# Crystal_Driver.net
KiCad netlist of a schematic drawn in EAGLE
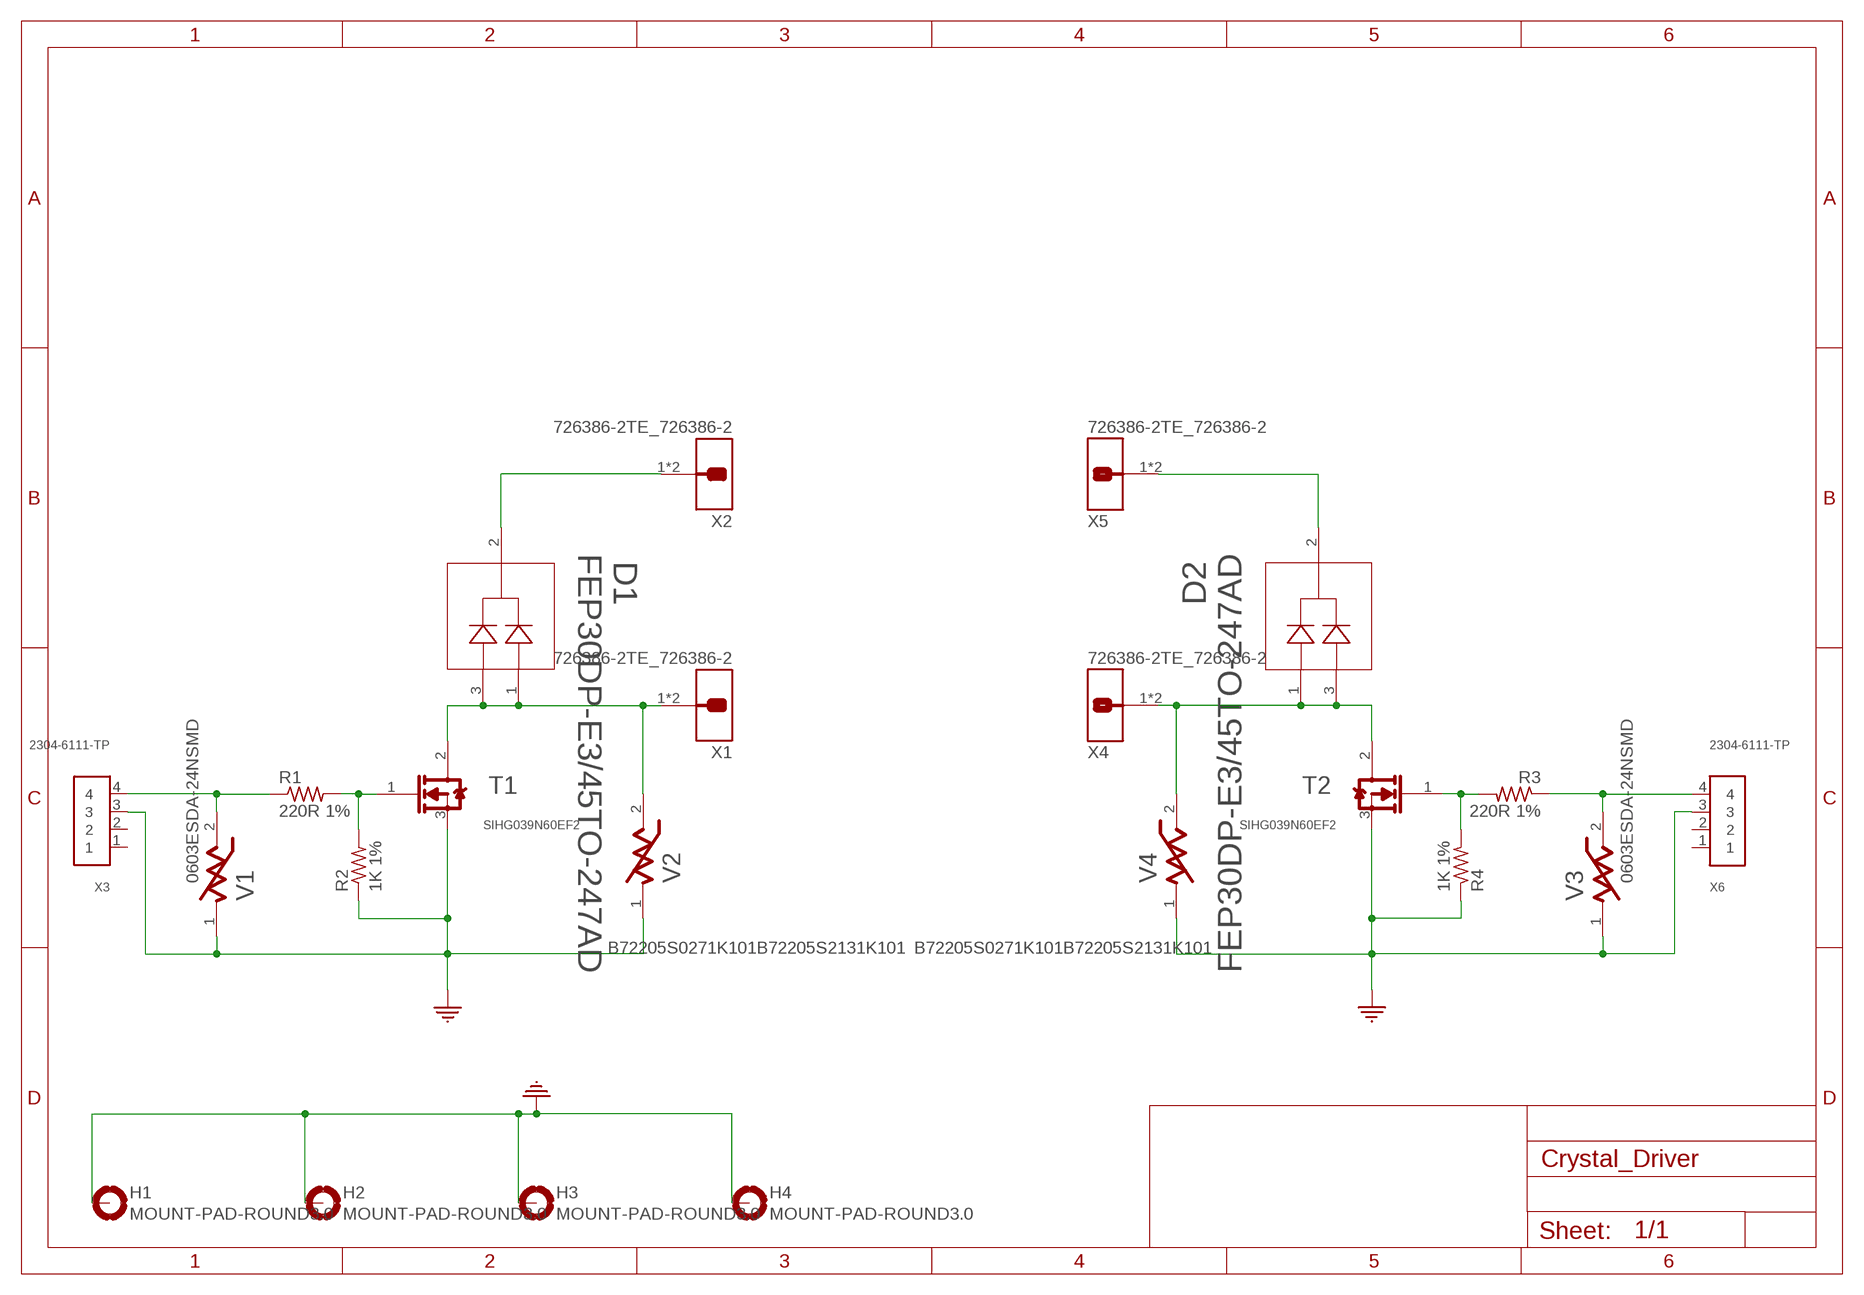
[diagram p0: schematic, sheet 1]

(export (version "E")
  (design (tool "Eeschema 10.0.6"))
  (components
    (comp (ref "D1")
      (value "FEP30DP-E3/45TO-247AD")
      (footprint "eagle-import:TO-247AD")
      (libsource (lib "eagle-import") (part "FEP30DP-E3/45TO-247AD"))
    )
    (comp (ref "D2")
      (value "FEP30DP-E3/45TO-247AD")
      (footprint "eagle-import:TO-247AD")
      (libsource (lib "eagle-import") (part "FEP30DP-E3/45TO-247AD"))
    )
    (comp (ref "H1")
      (value "MOUNT-PAD-ROUND3.0")
      (footprint "eagle-import:3,0-PAD")
      (libsource (lib "eagle-import") (part "MOUNT-PAD-ROUND3.0"))
    )
    (comp (ref "H2")
      (value "MOUNT-PAD-ROUND3.0")
      (footprint "eagle-import:3,0-PAD")
      (libsource (lib "eagle-import") (part "MOUNT-PAD-ROUND3.0"))
    )
    (comp (ref "H3")
      (value "MOUNT-PAD-ROUND3.0")
      (footprint "eagle-import:3,0-PAD")
      (libsource (lib "eagle-import") (part "MOUNT-PAD-ROUND3.0"))
    )
    (comp (ref "H4")
      (value "MOUNT-PAD-ROUND3.0")
      (footprint "eagle-import:3,0-PAD")
      (libsource (lib "eagle-import") (part "MOUNT-PAD-ROUND3.0"))
    )
    (comp (ref "R1")
      (value "220R 1%")
      (footprint "eagle-import:EIA1206")
      (libsource (lib "eagle-import") (part "R_1206EIA1206"))
    )
    (comp (ref "R2")
      (value "1K 1%")
      (footprint "eagle-import:EIA0603")
      (libsource (lib "eagle-import") (part "R_0603"))
    )
    (comp (ref "R3")
      (value "220R 1%")
      (footprint "eagle-import:EIA1206")
      (libsource (lib "eagle-import") (part "R_1206EIA1206"))
    )
    (comp (ref "R4")
      (value "1K 1%")
      (footprint "eagle-import:EIA0603")
      (libsource (lib "eagle-import") (part "R_0603"))
    )
    (comp (ref "T1")
      (value "SIHG039N60EF2")
      (footprint "eagle-import:TO-247AC")
      (libsource (lib "eagle-import") (part "SIHG039N60EF2"))
    )
    (comp (ref "T2")
      (value "SIHG039N60EF2")
      (footprint "eagle-import:TO-247AC")
      (libsource (lib "eagle-import") (part "SIHG039N60EF2"))
    )
    (comp (ref "V1")
      (value "0603ESDA-24NSMD")
      (footprint "eagle-import:EIA0603")
      (fields (field (name "MFR") "Bourns"))
      (libsource (lib "eagle-import") (part "0603ESDA-24NSMD"))
    )
    (comp (ref "V2")
      (value "B72205S0271K101B72205S2131K101")
      (footprint "eagle-import:EPCOS_B72205S0271K101_0")
      (fields (field (name "MFR") "EPCOS"))
      (libsource (lib "eagle-import") (part "B72205S0271K101B72205S2131K101"))
    )
    (comp (ref "V3")
      (value "0603ESDA-24NSMD")
      (footprint "eagle-import:EIA0603")
      (fields (field (name "MFR") "Bourns"))
      (libsource (lib "eagle-import") (part "0603ESDA-24NSMD"))
    )
    (comp (ref "V4")
      (value "B72205S0271K101B72205S2131K101")
      (footprint "eagle-import:EPCOS_B72205S0271K101_0")
      (fields (field (name "MFR") "EPCOS"))
      (libsource (lib "eagle-import") (part "B72205S0271K101B72205S2131K101"))
    )
    (comp (ref "X1")
      (value "726386-2TE_726386-2")
      (footprint "eagle-import:TE_726386-2")
      (fields
        (field (name "DIGIKEY_PART_NUMBER") "A114371-ND")
        (field (name "MF") "TE")
        (field (name "MOUSER_PART_NUMBER") "571-726386-2")
      )
      (libsource (lib "eagle-import") (part "726386-2TE_726386-2"))
    )
    (comp (ref "X2")
      (value "726386-2TE_726386-2")
      (footprint "eagle-import:TE_726386-2")
      (fields
        (field (name "DIGIKEY_PART_NUMBER") "A114371-ND")
        (field (name "MF") "TE")
        (field (name "MOUSER_PART_NUMBER") "571-726386-2")
      )
      (libsource (lib "eagle-import") (part "726386-2TE_726386-2"))
    )
    (comp (ref "X3")
      (value "2304-6111-TP")
      (footprint "eagle-import:X04_100MIL")
      (fields (field (name "MFR") "3M"))
      (libsource (lib "eagle-import") (part "2304-6111-TP"))
    )
    (comp (ref "X4")
      (value "726386-2TE_726386-2")
      (footprint "eagle-import:TE_726386-2")
      (fields
        (field (name "DIGIKEY_PART_NUMBER") "A114371-ND")
        (field (name "MF") "TE")
        (field (name "MOUSER_PART_NUMBER") "571-726386-2")
      )
      (libsource (lib "eagle-import") (part "726386-2TE_726386-2"))
    )
    (comp (ref "X5")
      (value "726386-2TE_726386-2")
      (footprint "eagle-import:TE_726386-2")
      (fields
        (field (name "DIGIKEY_PART_NUMBER") "A114371-ND")
        (field (name "MF") "TE")
        (field (name "MOUSER_PART_NUMBER") "571-726386-2")
      )
      (libsource (lib "eagle-import") (part "726386-2TE_726386-2"))
    )
    (comp (ref "X6")
      (value "2304-6111-TP")
      (footprint "eagle-import:X04_100MIL")
      (fields (field (name "MFR") "3M"))
      (libsource (lib "eagle-import") (part "2304-6111-TP"))
    )
  )
  (nets
    (net (code "1") (name "GND") (class "Default")
      (node (ref "H1") (pin "B3,0") (pinfunction "MOUNT_B3,0") (pintype "passive"))
      (node (ref "H2") (pin "B3,0") (pinfunction "MOUNT_B3,0") (pintype "passive"))
      (node (ref "H3") (pin "B3,0") (pinfunction "MOUNT_B3,0") (pintype "passive"))
      (node (ref "H4") (pin "B3,0") (pinfunction "MOUNT_B3,0") (pintype "passive"))
      (node (ref "R2") (pin "1") (pinfunction "1_1") (pintype "passive"))
      (node (ref "R4") (pin "1") (pinfunction "1_1") (pintype "passive"))
      (node (ref "T1") (pin "3") (pinfunction "S_3") (pintype "passive"))
      (node (ref "T2") (pin "3") (pinfunction "S_3") (pintype "passive"))
      (node (ref "V1") (pin "1") (pinfunction "1_1") (pintype "passive"))
      (node (ref "V2") (pin "1") (pinfunction "1_1") (pintype "passive"))
      (node (ref "V3") (pin "1") (pinfunction "1_1") (pintype "passive"))
      (node (ref "V4") (pin "1") (pinfunction "1_1") (pintype "passive"))
      (node (ref "X3") (pin "3") (pinfunction "3_3") (pintype "bidirectional"))
      (node (ref "X6") (pin "3") (pinfunction "3_3") (pintype "bidirectional"))
    )
    (net (code "2") (name "Net-(D1-Pad2)") (class "Default")
      (node (ref "D1") (pin "2") (pinfunction "2_2") (pintype "passive"))
      (node (ref "X2") (pin "1") (pinfunction "1_1") (pintype "passive"))
      (node (ref "X2") (pin "1-2") (pinfunction "1_1-2") (pintype "passive"))
    )
    (net (code "3") (name "Net-(D2-Pad2)") (class "Default")
      (node (ref "D2") (pin "2") (pinfunction "2_2") (pintype "passive"))
      (node (ref "X5") (pin "1") (pinfunction "1_1") (pintype "passive"))
      (node (ref "X5") (pin "1-2") (pinfunction "1_1-2") (pintype "passive"))
    )
    (net (code "4") (name "Net-(R1-Pad1)") (class "Default")
      (node (ref "R1") (pin "1") (pinfunction "1_1") (pintype "passive"))
      (node (ref "V1") (pin "2") (pinfunction "2_2") (pintype "passive"))
      (node (ref "X3") (pin "4") (pinfunction "4_4") (pintype "bidirectional"))
    )
    (net (code "5") (name "Net-(R3-Pad1)") (class "Default")
      (node (ref "R3") (pin "1") (pinfunction "1_1") (pintype "passive"))
      (node (ref "V3") (pin "2") (pinfunction "2_2") (pintype "passive"))
      (node (ref "X6") (pin "4") (pinfunction "4_4") (pintype "bidirectional"))
    )
    (net (code "6") (name "Net-(T1-D)") (class "Default")
      (node (ref "D1") (pin "1") (pinfunction "1_1") (pintype "passive"))
      (node (ref "D1") (pin "3") (pinfunction "3_3") (pintype "passive"))
      (node (ref "T1") (pin "2") (pinfunction "D_2") (pintype "passive"))
      (node (ref "V2") (pin "2") (pinfunction "2_2") (pintype "passive"))
      (node (ref "X1") (pin "1") (pinfunction "1_1") (pintype "passive"))
      (node (ref "X1") (pin "1-2") (pinfunction "1_1-2") (pintype "passive"))
    )
    (net (code "7") (name "Net-(T1-G)") (class "Default")
      (node (ref "R1") (pin "2") (pinfunction "2_2") (pintype "passive"))
      (node (ref "R2") (pin "2") (pinfunction "2_2") (pintype "passive"))
      (node (ref "T1") (pin "1") (pinfunction "G_1") (pintype "passive"))
    )
    (net (code "8") (name "Net-(T2-D)") (class "Default")
      (node (ref "D2") (pin "1") (pinfunction "1_1") (pintype "passive"))
      (node (ref "D2") (pin "3") (pinfunction "3_3") (pintype "passive"))
      (node (ref "T2") (pin "2") (pinfunction "D_2") (pintype "passive"))
      (node (ref "V4") (pin "2") (pinfunction "2_2") (pintype "passive"))
      (node (ref "X4") (pin "1") (pinfunction "1_1") (pintype "passive"))
      (node (ref "X4") (pin "1-2") (pinfunction "1_1-2") (pintype "passive"))
    )
    (net (code "9") (name "Net-(T2-G)") (class "Default")
      (node (ref "R3") (pin "2") (pinfunction "2_2") (pintype "passive"))
      (node (ref "R4") (pin "2") (pinfunction "2_2") (pintype "passive"))
      (node (ref "T2") (pin "1") (pinfunction "G_1") (pintype "passive"))
    )
    (net (code "10") (name "unconnected-(X3-Pad1)") (class "Default")
      (node (ref "X3") (pin "1") (pinfunction "1_1") (pintype "bidirectional"))
    )
    (net (code "11") (name "unconnected-(X3-Pad2)") (class "Default")
      (node (ref "X3") (pin "2") (pinfunction "2_2") (pintype "bidirectional"))
    )
    (net (code "12") (name "unconnected-(X6-Pad1)") (class "Default")
      (node (ref "X6") (pin "1") (pinfunction "1_1") (pintype "bidirectional"))
    )
    (net (code "13") (name "unconnected-(X6-Pad2)") (class "Default")
      (node (ref "X6") (pin "2") (pinfunction "2_2") (pintype "bidirectional"))
    )
  )
)
